# VESC_POWER_SCH.net
KiCad netlist of a schematic drawn in Altium Designer
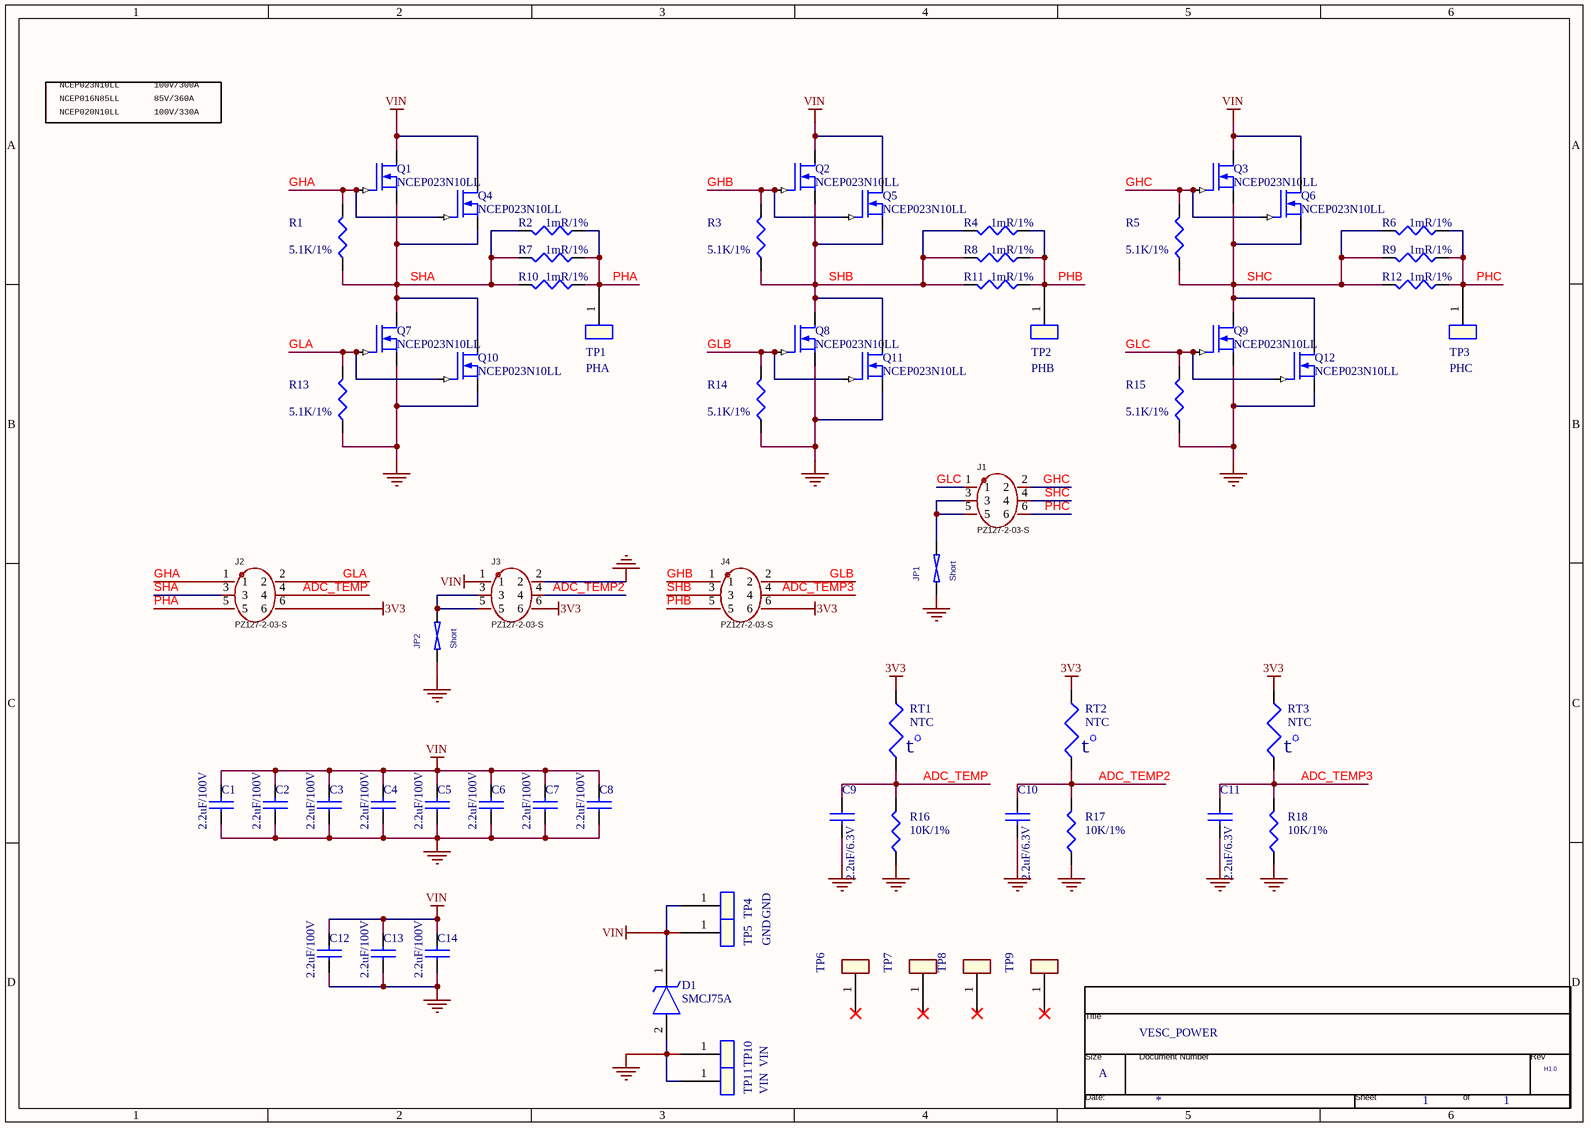
[diagram p0: VESC_POWER_SCH.SchDoc]

(export (version "E")
  (design (tool "Eeschema 10.0.6"))
  (components
    (comp (ref "*")
      (value "TitleBlock0")
      (fields
        (field (name "REVCODE") "H1.0")
        (field (name "TITLE") "VESC_POWER")
        (field (name "PAGE SIZE") "A")
        (field (name "PAGE NUMBER") "1")
        (field (name "PAGE COUNT") "1")
      )
      (libsource (lib "*") (part "TitleBlock0"))
    )
    (comp (ref "C1") (value "2.2uF/100V") (footprint "CAPC3225X230N") (libsource (lib "*") (part "CAP NP")))
    (comp (ref "C2") (value "2.2uF/100V") (footprint "CAPC3225X230N") (libsource (lib "*") (part "CAP NP")))
    (comp (ref "C3") (value "2.2uF/100V") (footprint "CAPC3225X230N") (libsource (lib "*") (part "CAP NP")))
    (comp (ref "C4") (value "2.2uF/100V") (footprint "CAPC3225X230N") (libsource (lib "*") (part "CAP NP")))
    (comp (ref "C5") (value "2.2uF/100V") (footprint "CAPC3225X230N") (libsource (lib "*") (part "CAP NP")))
    (comp (ref "C6") (value "2.2uF/100V") (footprint "CAPC3225X230N") (libsource (lib "*") (part "CAP NP")))
    (comp (ref "C7") (value "2.2uF/100V") (footprint "CAPC3225X230N") (libsource (lib "*") (part "CAP NP")))
    (comp (ref "C8") (value "2.2uF/100V") (footprint "CAPC3225X230N") (libsource (lib "*") (part "CAP NP")))
    (comp (ref "C9") (value "2.2uF/6.3V") (footprint "C0603") (libsource (lib "*") (part "CAP NP")))
    (comp (ref "C10") (value "2.2uF/6.3V") (footprint "C0603") (libsource (lib "*") (part "CAP NP")))
    (comp (ref "C11") (value "2.2uF/6.3V") (footprint "C0603") (libsource (lib "*") (part "CAP NP")))
    (comp (ref "C12") (value "2.2uF/100V") (footprint "CAPC3225X230N") (libsource (lib "*") (part "CAP NP")))
    (comp (ref "C13") (value "2.2uF/100V") (footprint "CAPC3225X230N") (libsource (lib "*") (part "CAP NP")))
    (comp (ref "C14") (value "2.2uF/100V") (footprint "CAPC3225X230N") (libsource (lib "*") (part "CAP NP")))
    (comp (ref "D1")
      (value "SMCJ75A")
      (footprint "DIOM7959X262N")
      (description "TVS Diode (Uni-directional)")
      (fields (field (name "MOUSER PART NUMBER") "652-SMCJ75A"))
      (libsource (lib "VESC_POWER_Library") (part "SMCJ75A"))
    )
    (comp (ref "J1")
      (value "PZ127-2-03-S")
      (footprint "HDR-SMD_6P-P1.27-V-M-R2-C3-LS5.3")
      (fields (field (name "MANUFACTURER") "HCTL(华灿天禄)"))
      (libsource (lib "VESC_POWER_Library") (part "PZ127-2-03-S"))
    )
    (comp (ref "J2")
      (value "PZ127-2-03-S")
      (footprint "HDR-SMD_6P-P1.27-V-M-R2-C3-LS5.3")
      (fields (field (name "MANUFACTURER") "HCTL(华灿天禄)"))
      (libsource (lib "VESC_POWER_Library") (part "PZ127-2-03-S"))
    )
    (comp (ref "J3")
      (value "PZ127-2-03-S")
      (footprint "HDR-SMD_6P-P1.27-V-M-R2-C3-LS5.3")
      (fields (field (name "MANUFACTURER") "HCTL(华灿天禄)"))
      (libsource (lib "VESC_POWER_Library") (part "PZ127-2-03-S"))
    )
    (comp (ref "J4")
      (value "PZ127-2-03-S")
      (footprint "HDR-SMD_6P-P1.27-V-M-R2-C3-LS5.3")
      (fields (field (name "MANUFACTURER") "HCTL(华灿天禄)"))
      (libsource (lib "VESC_POWER_Library") (part "PZ127-2-03-S"))
    )
    (comp (ref "JP1")
      (value "Short")
      (footprint "SHORT")
      (description "2 PIN SHORTED TO CONNECT DIFFERENT NETS")
      (fields (field (name "PART_NUMBER") "TMP-442"))
      (libsource (lib "VESC_POWER_Library") (part "SHORT"))
    )
    (comp (ref "JP2")
      (value "Short")
      (footprint "SHORT")
      (description "2 PIN SHORTED TO CONNECT DIFFERENT NETS")
      (fields (field (name "PART_NUMBER") "TMP-442"))
      (libsource (lib "VESC_POWER_Library") (part "SHORT"))
    )
    (comp (ref "Q1") (value "NCEP023N10LL") (footprint "TOLL") (libsource (lib "*") (part "MOSFET N")))
    (comp (ref "Q2") (value "NCEP023N10LL") (footprint "TOLL") (libsource (lib "*") (part "MOSFET N")))
    (comp (ref "Q3") (value "NCEP023N10LL") (footprint "TOLL") (libsource (lib "*") (part "MOSFET N")))
    (comp (ref "Q4") (value "NCEP023N10LL") (footprint "TOLL") (libsource (lib "*") (part "MOSFET N")))
    (comp (ref "Q5") (value "NCEP023N10LL") (footprint "TOLL") (libsource (lib "*") (part "MOSFET N")))
    (comp (ref "Q6") (value "NCEP023N10LL") (footprint "TOLL") (libsource (lib "*") (part "MOSFET N")))
    (comp (ref "Q7") (value "NCEP023N10LL") (footprint "TOLL") (libsource (lib "*") (part "MOSFET N")))
    (comp (ref "Q8") (value "NCEP023N10LL") (footprint "TOLL") (libsource (lib "*") (part "MOSFET N")))
    (comp (ref "Q9") (value "NCEP023N10LL") (footprint "TOLL") (libsource (lib "*") (part "MOSFET N")))
    (comp (ref "Q10") (value "NCEP023N10LL") (footprint "TOLL") (libsource (lib "*") (part "MOSFET N")))
    (comp (ref "Q11") (value "NCEP023N10LL") (footprint "TOLL") (libsource (lib "*") (part "MOSFET N")))
    (comp (ref "Q12") (value "NCEP023N10LL") (footprint "TOLL") (libsource (lib "*") (part "MOSFET N")))
    (comp (ref "R1") (value "5.1K/1%") (footprint "R0603") (libsource (lib "*") (part "RESISTOR")))
    (comp (ref "R2") (value "1mR/1%") (footprint "R2512") (libsource (lib "*") (part "RESISTOR")))
    (comp (ref "R3") (value "5.1K/1%") (footprint "R0603") (libsource (lib "*") (part "RESISTOR")))
    (comp (ref "R4") (value "1mR/1%") (footprint "R2512") (libsource (lib "*") (part "RESISTOR")))
    (comp (ref "R5") (value "5.1K/1%") (footprint "R0603") (libsource (lib "*") (part "RESISTOR")))
    (comp (ref "R6") (value "1mR/1%") (footprint "R2512") (libsource (lib "*") (part "RESISTOR")))
    (comp (ref "R7") (value "1mR/1%") (footprint "R2512") (libsource (lib "*") (part "RESISTOR")))
    (comp (ref "R8") (value "1mR/1%") (footprint "R2512") (libsource (lib "*") (part "RESISTOR")))
    (comp (ref "R9") (value "1mR/1%") (footprint "R2512") (libsource (lib "*") (part "RESISTOR")))
    (comp (ref "R10") (value "1mR/1%") (footprint "R2512") (libsource (lib "*") (part "RESISTOR")))
    (comp (ref "R11") (value "1mR/1%") (footprint "R2512") (libsource (lib "*") (part "RESISTOR")))
    (comp (ref "R12") (value "1mR/1%") (footprint "R2512") (libsource (lib "*") (part "RESISTOR")))
    (comp (ref "R13") (value "5.1K/1%") (footprint "R0603") (libsource (lib "*") (part "RESISTOR")))
    (comp (ref "R14") (value "5.1K/1%") (footprint "R0603") (libsource (lib "*") (part "RESISTOR")))
    (comp (ref "R15") (value "5.1K/1%") (footprint "R0603") (libsource (lib "*") (part "RESISTOR")))
    (comp (ref "R16") (value "10K/1%") (footprint "R0603") (libsource (lib "*") (part "RESISTOR")))
    (comp (ref "R17") (value "10K/1%") (footprint "R0603") (libsource (lib "*") (part "RESISTOR")))
    (comp (ref "R18") (value "10K/1%") (footprint "R0603") (libsource (lib "*") (part "RESISTOR")))
    (comp (ref "RT1") (value "NTC") (footprint "R0603") (libsource (lib "*") (part "NTC")))
    (comp (ref "RT2") (value "NTC") (footprint "R0603") (libsource (lib "*") (part "NTC")))
    (comp (ref "RT3") (value "NTC") (footprint "R0603") (libsource (lib "*") (part "NTC")))
    (comp (ref "TP1") (value "PHA") (footprint "TP_11X11") (libsource (lib "") (part "TEST POINT_1")))
    (comp (ref "TP2") (value "PHB") (footprint "TP_11X11") (libsource (lib "") (part "TEST POINT_1")))
    (comp (ref "TP3") (value "PHC") (footprint "TP_11X11") (libsource (lib "") (part "TEST POINT_1")))
    (comp (ref "TP4") (value "GND") (footprint "TP_7X7") (libsource (lib "*") (part "TEST POINT")))
    (comp (ref "TP5") (value "GND") (footprint "TP_11X11") (libsource (lib "*") (part "TEST POINT")))
    (comp (ref "TP6")
      (value "TEST POINT")
      (footprint "HOLE-3.2MM_M")
      (libsource (lib "VESC_POWER_Library") (part "TEST POINT"))
    )
    (comp (ref "TP7")
      (value "TEST POINT")
      (footprint "HOLE-3.2MM_M")
      (libsource (lib "VESC_POWER_Library") (part "TEST POINT"))
    )
    (comp (ref "TP8")
      (value "TEST POINT")
      (footprint "HOLE-3.2MM_M")
      (libsource (lib "VESC_POWER_Library") (part "TEST POINT"))
    )
    (comp (ref "TP9")
      (value "TEST POINT")
      (footprint "HOLE-3.2MM_M")
      (libsource (lib "VESC_POWER_Library") (part "TEST POINT"))
    )
    (comp (ref "TP10") (value "VIN") (footprint "TP_11X11") (libsource (lib "*") (part "TEST POINT")))
    (comp (ref "TP11") (value "VIN") (footprint "TP_7X7") (libsource (lib "*") (part "TEST POINT")))
  )
  (nets
    (net (code "1") (name "/ADC_TEMP") (class "Default")
      (node (ref "C9") (pin "1") (pinfunction "1_1") (pintype "passive"))
      (node (ref "J2") (pin "4") (pinfunction "4_4") (pintype "passive"))
      (node (ref "R16") (pin "2") (pinfunction "2_2") (pintype "passive"))
      (node (ref "RT1") (pin "2") (pinfunction "2_2") (pintype "passive"))
    )
    (net (code "2") (name "/ADC_TEMP2") (class "Default")
      (node (ref "C10") (pin "1") (pinfunction "1_1") (pintype "passive"))
      (node (ref "J3") (pin "4") (pinfunction "4_4") (pintype "passive"))
      (node (ref "R17") (pin "2") (pinfunction "2_2") (pintype "passive"))
      (node (ref "RT2") (pin "2") (pinfunction "2_2") (pintype "passive"))
    )
    (net (code "3") (name "/ADC_TEMP3") (class "Default")
      (node (ref "C11") (pin "1") (pinfunction "1_1") (pintype "passive"))
      (node (ref "J4") (pin "4") (pinfunction "4_4") (pintype "passive"))
      (node (ref "R18") (pin "2") (pinfunction "2_2") (pintype "passive"))
      (node (ref "RT3") (pin "2") (pinfunction "2_2") (pintype "passive"))
    )
    (net (code "4") (name "/GHA") (class "Default")
      (node (ref "J2") (pin "1") (pinfunction "1_1") (pintype "passive"))
      (node (ref "Q1") (pin "1") (pinfunction "GATE_1") (pintype "input"))
      (node (ref "Q4") (pin "1") (pinfunction "GATE_1") (pintype "input"))
      (node (ref "R1") (pin "2") (pinfunction "2_2") (pintype "passive"))
    )
    (net (code "5") (name "/GHB") (class "Default")
      (node (ref "J4") (pin "1") (pinfunction "1_1") (pintype "passive"))
      (node (ref "Q2") (pin "1") (pinfunction "GATE_1") (pintype "input"))
      (node (ref "Q5") (pin "1") (pinfunction "GATE_1") (pintype "input"))
      (node (ref "R3") (pin "2") (pinfunction "2_2") (pintype "passive"))
    )
    (net (code "6") (name "/GHC") (class "Default")
      (node (ref "J1") (pin "2") (pinfunction "2_2") (pintype "passive"))
      (node (ref "Q3") (pin "1") (pinfunction "GATE_1") (pintype "input"))
      (node (ref "Q6") (pin "1") (pinfunction "GATE_1") (pintype "input"))
      (node (ref "R5") (pin "2") (pinfunction "2_2") (pintype "passive"))
    )
    (net (code "7") (name "/GLA") (class "Default")
      (node (ref "J2") (pin "2") (pinfunction "2_2") (pintype "passive"))
      (node (ref "Q10") (pin "1") (pinfunction "GATE_1") (pintype "input"))
      (node (ref "Q7") (pin "1") (pinfunction "GATE_1") (pintype "input"))
      (node (ref "R13") (pin "2") (pinfunction "2_2") (pintype "passive"))
    )
    (net (code "8") (name "/GLB") (class "Default")
      (node (ref "J4") (pin "2") (pinfunction "2_2") (pintype "passive"))
      (node (ref "Q11") (pin "1") (pinfunction "GATE_1") (pintype "input"))
      (node (ref "Q8") (pin "1") (pinfunction "GATE_1") (pintype "input"))
      (node (ref "R14") (pin "2") (pinfunction "2_2") (pintype "passive"))
    )
    (net (code "9") (name "/GLC") (class "Default")
      (node (ref "J1") (pin "1") (pinfunction "1_1") (pintype "passive"))
      (node (ref "Q12") (pin "1") (pinfunction "GATE_1") (pintype "input"))
      (node (ref "Q9") (pin "1") (pinfunction "GATE_1") (pintype "input"))
      (node (ref "R15") (pin "2") (pinfunction "2_2") (pintype "passive"))
    )
    (net (code "10") (name "/PHA") (class "Default")
      (node (ref "J2") (pin "5") (pinfunction "5_5") (pintype "passive"))
      (node (ref "R10") (pin "1") (pinfunction "1_1") (pintype "passive"))
      (node (ref "R2") (pin "1") (pinfunction "1_1") (pintype "passive"))
      (node (ref "R7") (pin "1") (pinfunction "1_1") (pintype "passive"))
      (node (ref "TP1") (pin "1") (pinfunction "1_1") (pintype "passive"))
    )
    (net (code "11") (name "/PHB") (class "Default")
      (node (ref "J4") (pin "5") (pinfunction "5_5") (pintype "passive"))
      (node (ref "R11") (pin "1") (pinfunction "1_1") (pintype "passive"))
      (node (ref "R4") (pin "1") (pinfunction "1_1") (pintype "passive"))
      (node (ref "R8") (pin "1") (pinfunction "1_1") (pintype "passive"))
      (node (ref "TP2") (pin "1") (pinfunction "1_1") (pintype "passive"))
    )
    (net (code "12") (name "/PHC") (class "Default")
      (node (ref "J1") (pin "6") (pinfunction "6_6") (pintype "passive"))
      (node (ref "R12") (pin "1") (pinfunction "1_1") (pintype "passive"))
      (node (ref "R6") (pin "1") (pinfunction "1_1") (pintype "passive"))
      (node (ref "R9") (pin "1") (pinfunction "1_1") (pintype "passive"))
      (node (ref "TP3") (pin "1") (pinfunction "1_1") (pintype "passive"))
    )
    (net (code "13") (name "/SHA") (class "Default")
      (node (ref "J2") (pin "3") (pinfunction "3_3") (pintype "passive"))
      (node (ref "Q1") (pin "3") (pinfunction "SOURCE_3") (pintype "passive"))
      (node (ref "Q10") (pin "2") (pinfunction "DRAIN_2") (pintype "passive"))
      (node (ref "Q4") (pin "3") (pinfunction "SOURCE_3") (pintype "passive"))
      (node (ref "Q7") (pin "2") (pinfunction "DRAIN_2") (pintype "passive"))
      (node (ref "R1") (pin "1") (pinfunction "1_1") (pintype "passive"))
      (node (ref "R10") (pin "2") (pinfunction "2_2") (pintype "passive"))
      (node (ref "R2") (pin "2") (pinfunction "2_2") (pintype "passive"))
      (node (ref "R7") (pin "2") (pinfunction "2_2") (pintype "passive"))
    )
    (net (code "14") (name "/SHB") (class "Default")
      (node (ref "J4") (pin "3") (pinfunction "3_3") (pintype "passive"))
      (node (ref "Q11") (pin "2") (pinfunction "DRAIN_2") (pintype "passive"))
      (node (ref "Q2") (pin "3") (pinfunction "SOURCE_3") (pintype "passive"))
      (node (ref "Q5") (pin "3") (pinfunction "SOURCE_3") (pintype "passive"))
      (node (ref "Q8") (pin "2") (pinfunction "DRAIN_2") (pintype "passive"))
      (node (ref "R11") (pin "2") (pinfunction "2_2") (pintype "passive"))
      (node (ref "R3") (pin "1") (pinfunction "1_1") (pintype "passive"))
      (node (ref "R4") (pin "2") (pinfunction "2_2") (pintype "passive"))
      (node (ref "R8") (pin "2") (pinfunction "2_2") (pintype "passive"))
    )
    (net (code "15") (name "/SHC") (class "Default")
      (node (ref "J1") (pin "4") (pinfunction "4_4") (pintype "passive"))
      (node (ref "Q12") (pin "2") (pinfunction "DRAIN_2") (pintype "passive"))
      (node (ref "Q3") (pin "3") (pinfunction "SOURCE_3") (pintype "passive"))
      (node (ref "Q6") (pin "3") (pinfunction "SOURCE_3") (pintype "passive"))
      (node (ref "Q9") (pin "2") (pinfunction "DRAIN_2") (pintype "passive"))
      (node (ref "R12") (pin "2") (pinfunction "2_2") (pintype "passive"))
      (node (ref "R5") (pin "1") (pinfunction "1_1") (pintype "passive"))
      (node (ref "R6") (pin "2") (pinfunction "2_2") (pintype "passive"))
      (node (ref "R9") (pin "2") (pinfunction "2_2") (pintype "passive"))
    )
    (net (code "16") (name "3V3") (class "Default")
      (node (ref "J2") (pin "6") (pinfunction "6_6") (pintype "passive"))
      (node (ref "J3") (pin "6") (pinfunction "6_6") (pintype "passive"))
      (node (ref "J4") (pin "6") (pinfunction "6_6") (pintype "passive"))
      (node (ref "RT1") (pin "1") (pinfunction "1_1") (pintype "passive"))
      (node (ref "RT2") (pin "1") (pinfunction "1_1") (pintype "passive"))
      (node (ref "RT3") (pin "1") (pinfunction "1_1") (pintype "passive"))
    )
    (net (code "17") (name "GND") (class "Default")
      (node (ref "C1") (pin "1") (pinfunction "1_1") (pintype "passive"))
      (node (ref "C10") (pin "2") (pinfunction "2_2") (pintype "passive"))
      (node (ref "C11") (pin "2") (pinfunction "2_2") (pintype "passive"))
      (node (ref "C12") (pin "1") (pinfunction "1_1") (pintype "passive"))
      (node (ref "C13") (pin "1") (pinfunction "1_1") (pintype "passive"))
      (node (ref "C14") (pin "1") (pinfunction "1_1") (pintype "passive"))
      (node (ref "C2") (pin "1") (pinfunction "1_1") (pintype "passive"))
      (node (ref "C3") (pin "1") (pinfunction "1_1") (pintype "passive"))
      (node (ref "C4") (pin "1") (pinfunction "1_1") (pintype "passive"))
      (node (ref "C5") (pin "1") (pinfunction "1_1") (pintype "passive"))
      (node (ref "C6") (pin "1") (pinfunction "1_1") (pintype "passive"))
      (node (ref "C7") (pin "1") (pinfunction "1_1") (pintype "passive"))
      (node (ref "C8") (pin "1") (pinfunction "1_1") (pintype "passive"))
      (node (ref "C9") (pin "2") (pinfunction "2_2") (pintype "passive"))
      (node (ref "D1") (pin "2") (pinfunction "A_2") (pintype "passive"))
      (node (ref "J3") (pin "2") (pinfunction "2_2") (pintype "passive"))
      (node (ref "JP1") (pin "1") (pinfunction "1_1") (pintype "passive"))
      (node (ref "JP2") (pin "1") (pinfunction "1_1") (pintype "passive"))
      (node (ref "Q10") (pin "3") (pinfunction "SOURCE_3") (pintype "passive"))
      (node (ref "Q11") (pin "3") (pinfunction "SOURCE_3") (pintype "passive"))
      (node (ref "Q12") (pin "3") (pinfunction "SOURCE_3") (pintype "passive"))
      (node (ref "Q7") (pin "3") (pinfunction "SOURCE_3") (pintype "passive"))
      (node (ref "Q8") (pin "3") (pinfunction "SOURCE_3") (pintype "passive"))
      (node (ref "Q9") (pin "3") (pinfunction "SOURCE_3") (pintype "passive"))
      (node (ref "R13") (pin "1") (pinfunction "1_1") (pintype "passive"))
      (node (ref "R14") (pin "1") (pinfunction "1_1") (pintype "passive"))
      (node (ref "R15") (pin "1") (pinfunction "1_1") (pintype "passive"))
      (node (ref "R16") (pin "1") (pinfunction "1_1") (pintype "passive"))
      (node (ref "R17") (pin "1") (pinfunction "1_1") (pintype "passive"))
      (node (ref "R18") (pin "1") (pinfunction "1_1") (pintype "passive"))
      (node (ref "TP10") (pin "1") (pinfunction "1_1") (pintype "passive"))
      (node (ref "TP11") (pin "1") (pinfunction "1_1") (pintype "passive"))
    )
    (net (code "18") (name "Net-(J1-Pad3)") (class "Default")
      (node (ref "J1") (pin "3") (pinfunction "3_3") (pintype "passive"))
      (node (ref "J1") (pin "5") (pinfunction "5_5") (pintype "passive"))
      (node (ref "JP1") (pin "2") (pinfunction "2_2") (pintype "passive"))
    )
    (net (code "19") (name "Net-(J3-Pad3)") (class "Default")
      (node (ref "J3") (pin "3") (pinfunction "3_3") (pintype "passive"))
      (node (ref "J3") (pin "5") (pinfunction "5_5") (pintype "passive"))
      (node (ref "JP2") (pin "2") (pinfunction "2_2") (pintype "passive"))
    )
    (net (code "20") (name "VIN") (class "Default")
      (node (ref "C1") (pin "2") (pinfunction "2_2") (pintype "passive"))
      (node (ref "C12") (pin "2") (pinfunction "2_2") (pintype "passive"))
      (node (ref "C13") (pin "2") (pinfunction "2_2") (pintype "passive"))
      (node (ref "C14") (pin "2") (pinfunction "2_2") (pintype "passive"))
      (node (ref "C2") (pin "2") (pinfunction "2_2") (pintype "passive"))
      (node (ref "C3") (pin "2") (pinfunction "2_2") (pintype "passive"))
      (node (ref "C4") (pin "2") (pinfunction "2_2") (pintype "passive"))
      (node (ref "C5") (pin "2") (pinfunction "2_2") (pintype "passive"))
      (node (ref "C6") (pin "2") (pinfunction "2_2") (pintype "passive"))
      (node (ref "C7") (pin "2") (pinfunction "2_2") (pintype "passive"))
      (node (ref "C8") (pin "2") (pinfunction "2_2") (pintype "passive"))
      (node (ref "D1") (pin "1") (pinfunction "K_1") (pintype "passive"))
      (node (ref "J3") (pin "1") (pinfunction "1_1") (pintype "passive"))
      (node (ref "Q1") (pin "2") (pinfunction "DRAIN_2") (pintype "passive"))
      (node (ref "Q2") (pin "2") (pinfunction "DRAIN_2") (pintype "passive"))
      (node (ref "Q3") (pin "2") (pinfunction "DRAIN_2") (pintype "passive"))
      (node (ref "Q4") (pin "2") (pinfunction "DRAIN_2") (pintype "passive"))
      (node (ref "Q5") (pin "2") (pinfunction "DRAIN_2") (pintype "passive"))
      (node (ref "Q6") (pin "2") (pinfunction "DRAIN_2") (pintype "passive"))
      (node (ref "TP4") (pin "1") (pinfunction "1_1") (pintype "passive"))
      (node (ref "TP5") (pin "1") (pinfunction "1_1") (pintype "passive"))
    )
    (net (code "21") (name "unconnected-(TP6-Pad1)") (class "Default")
      (node (ref "TP6") (pin "1") (pinfunction "1_1") (pintype "passive+no_connect"))
    )
    (net (code "22") (name "unconnected-(TP7-Pad1)") (class "Default")
      (node (ref "TP7") (pin "1") (pinfunction "1_1") (pintype "passive+no_connect"))
    )
    (net (code "23") (name "unconnected-(TP8-Pad1)") (class "Default")
      (node (ref "TP8") (pin "1") (pinfunction "1_1") (pintype "passive+no_connect"))
    )
    (net (code "24") (name "unconnected-(TP9-Pad1)") (class "Default")
      (node (ref "TP9") (pin "1") (pinfunction "1_1") (pintype "passive+no_connect"))
    )
  )
)
